# IceBoard-Rev2.net
KiCad netlist of a schematic drawn in EAGLE
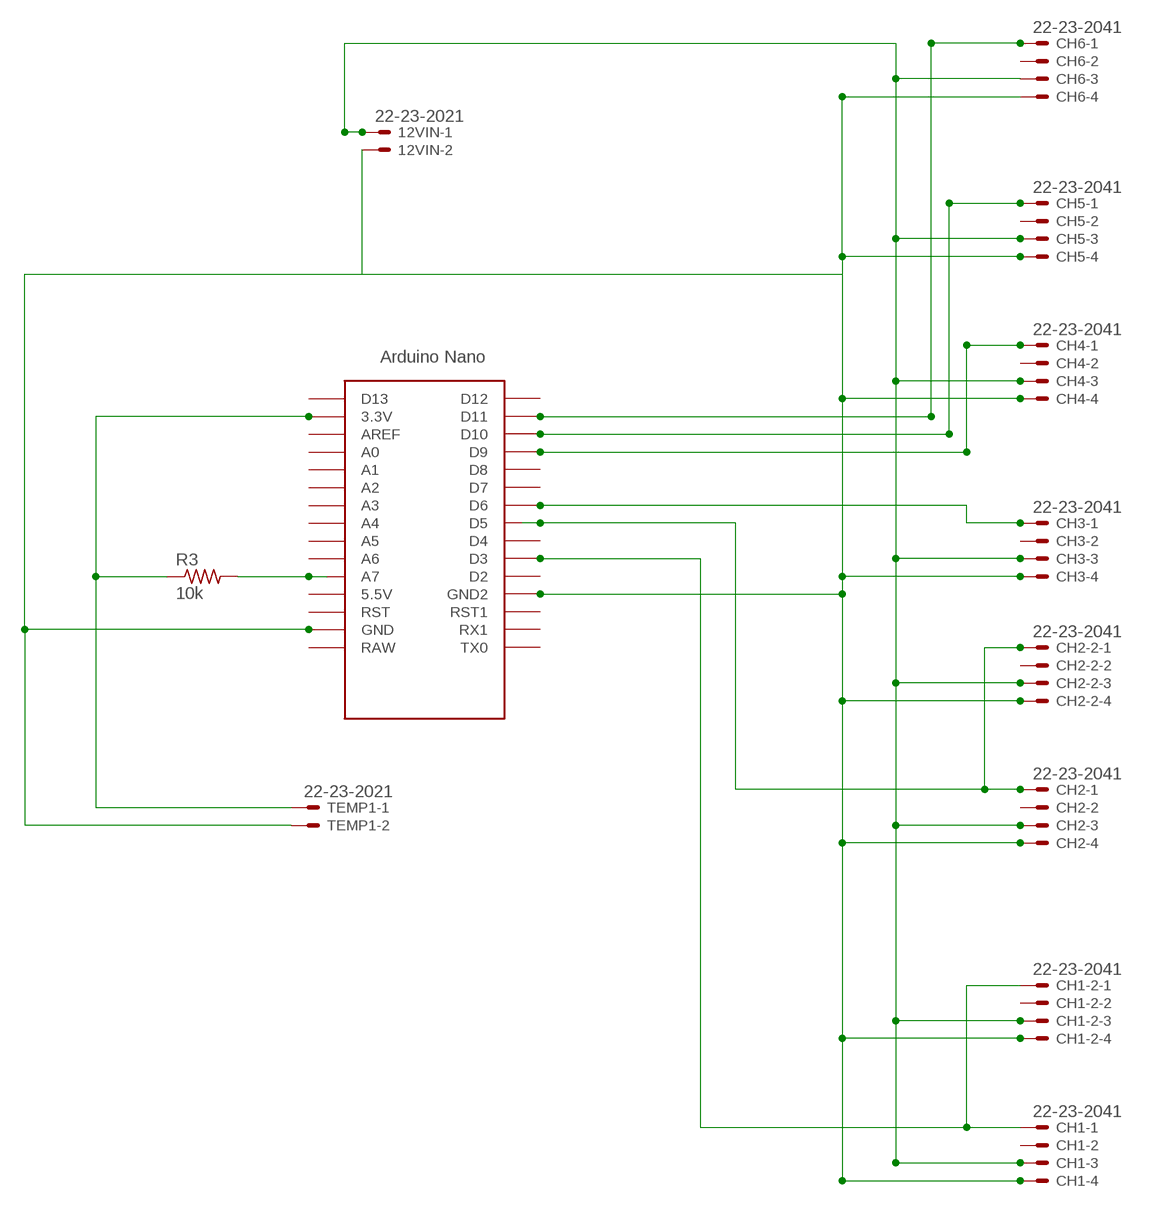
[diagram p0: schematic, sheet 1]

(export (version "E")
  (design (tool "Eeschema 10.0.6"))
  (components
    (comp (ref "12VIN")
      (value "22-23-2021")
      (footprint "eagle-import:22-23-2021")
      (fields (field (name "MF") "MOLEX"))
      (libsource (lib "eagle-import") (part "22-23-2021"))
    )
    (comp (ref "CH1")
      (value "22-23-2041")
      (footprint "eagle-import:22-23-2041")
      (fields (field (name "MF") "MOLEX"))
      (libsource (lib "eagle-import") (part "22-23-2041"))
    )
    (comp (ref "CH1-2")
      (value "22-23-2041")
      (footprint "eagle-import:22-23-2041")
      (fields (field (name "MF") "MOLEX"))
      (libsource (lib "eagle-import") (part "22-23-2041"))
    )
    (comp (ref "CH2")
      (value "22-23-2041")
      (footprint "eagle-import:22-23-2041")
      (fields (field (name "MF") "MOLEX"))
      (libsource (lib "eagle-import") (part "22-23-2041"))
    )
    (comp (ref "CH2-2")
      (value "22-23-2041")
      (footprint "eagle-import:22-23-2041")
      (fields (field (name "MF") "MOLEX"))
      (libsource (lib "eagle-import") (part "22-23-2041"))
    )
    (comp (ref "CH3")
      (value "22-23-2041")
      (footprint "eagle-import:22-23-2041")
      (fields (field (name "MF") "MOLEX"))
      (libsource (lib "eagle-import") (part "22-23-2041"))
    )
    (comp (ref "CH4")
      (value "22-23-2041")
      (footprint "eagle-import:22-23-2041")
      (fields (field (name "MF") "MOLEX"))
      (libsource (lib "eagle-import") (part "22-23-2041"))
    )
    (comp (ref "CH5")
      (value "22-23-2041")
      (footprint "eagle-import:22-23-2041")
      (fields (field (name "MF") "MOLEX"))
      (libsource (lib "eagle-import") (part "22-23-2041"))
    )
    (comp (ref "CH6")
      (value "22-23-2041")
      (footprint "eagle-import:22-23-2041")
      (fields (field (name "MF") "MOLEX"))
      (libsource (lib "eagle-import") (part "22-23-2041"))
    )
    (comp (ref "R3")
      (value "10k")
      (footprint "eagle-import:R0805")
      (libsource (lib "eagle-import") (part "R-US_R0805"))
    )
    (comp (ref "TEMP1")
      (value "22-23-2021")
      (footprint "eagle-import:22-23-2021")
      (fields (field (name "MF") "MOLEX"))
      (libsource (lib "eagle-import") (part "22-23-2021"))
    )
    (comp (ref "U$1")
      (value "NANO")
      (footprint "eagle-import:NANO")
      (libsource (lib "eagle-import") (part "NANO"))
    )
  )
  (nets
    (net (code "1") (name "Net-(12VINA-S)") (class "Default")
      (node (ref "12VIN") (pin "1") (pinfunction "S_1") (pintype "passive"))
      (node (ref "CH1") (pin "3") (pinfunction "S_3") (pintype "passive"))
      (node (ref "CH1-2") (pin "3") (pinfunction "S_3") (pintype "passive"))
      (node (ref "CH2") (pin "3") (pinfunction "S_3") (pintype "passive"))
      (node (ref "CH2-2") (pin "3") (pinfunction "S_3") (pintype "passive"))
      (node (ref "CH3") (pin "3") (pinfunction "S_3") (pintype "passive"))
      (node (ref "CH4") (pin "3") (pinfunction "S_3") (pintype "passive"))
      (node (ref "CH5") (pin "3") (pinfunction "S_3") (pintype "passive"))
      (node (ref "CH6") (pin "3") (pinfunction "S_3") (pintype "passive"))
    )
    (net (code "2") (name "Net-(12VINB-S)") (class "Default")
      (node (ref "12VIN") (pin "2") (pinfunction "S_2") (pintype "passive"))
      (node (ref "CH1") (pin "4") (pinfunction "S_4") (pintype "passive"))
      (node (ref "CH1-2") (pin "4") (pinfunction "S_4") (pintype "passive"))
      (node (ref "CH2") (pin "4") (pinfunction "S_4") (pintype "passive"))
      (node (ref "CH2-2") (pin "4") (pinfunction "S_4") (pintype "passive"))
      (node (ref "CH3") (pin "4") (pinfunction "S_4") (pintype "passive"))
      (node (ref "CH4") (pin "4") (pinfunction "S_4") (pintype "passive"))
      (node (ref "CH5") (pin "4") (pinfunction "S_4") (pintype "passive"))
      (node (ref "CH6") (pin "4") (pinfunction "S_4") (pintype "passive"))
      (node (ref "TEMP1") (pin "2") (pinfunction "S_2") (pintype "passive"))
      (node (ref "U$1") (pin "GND") (pinfunction "GND_GND") (pintype "bidirectional"))
      (node (ref "U$1") (pin "GND1") (pinfunction "GND2_GND1") (pintype "bidirectional"))
    )
    (net (code "3") (name "Net-(CH1-2A-S)") (class "Default")
      (node (ref "CH1") (pin "1") (pinfunction "S_1") (pintype "passive"))
      (node (ref "CH1-2") (pin "1") (pinfunction "S_1") (pintype "passive"))
      (node (ref "U$1") (pin "D3") (pinfunction "D3_D3") (pintype "bidirectional"))
    )
    (net (code "4") (name "Net-(CH2-2A-S)") (class "Default")
      (node (ref "CH2") (pin "1") (pinfunction "S_1") (pintype "passive"))
      (node (ref "CH2-2") (pin "1") (pinfunction "S_1") (pintype "passive"))
      (node (ref "U$1") (pin "D5") (pinfunction "D5_D5") (pintype "bidirectional"))
    )
    (net (code "5") (name "Net-(CH3A-S)") (class "Default")
      (node (ref "CH3") (pin "1") (pinfunction "S_1") (pintype "passive"))
      (node (ref "U$1") (pin "D6") (pinfunction "D6_D6") (pintype "bidirectional"))
    )
    (net (code "6") (name "Net-(CH4A-S)") (class "Default")
      (node (ref "CH4") (pin "1") (pinfunction "S_1") (pintype "passive"))
      (node (ref "U$1") (pin "D9") (pinfunction "D9_D9") (pintype "bidirectional"))
    )
    (net (code "7") (name "Net-(CH5A-S)") (class "Default")
      (node (ref "CH5") (pin "1") (pinfunction "S_1") (pintype "passive"))
      (node (ref "U$1") (pin "D10") (pinfunction "D10_D10") (pintype "bidirectional"))
    )
    (net (code "8") (name "Net-(CH6A-S)") (class "Default")
      (node (ref "CH6") (pin "1") (pinfunction "S_1") (pintype "passive"))
      (node (ref "U$1") (pin "D11") (pinfunction "D11_D11") (pintype "bidirectional"))
    )
    (net (code "9") (name "Net-(R3-Pad2)") (class "Default")
      (node (ref "R3") (pin "2") (pinfunction "2_2") (pintype "passive"))
      (node (ref "U$1") (pin "A7") (pinfunction "A7_A7") (pintype "bidirectional"))
    )
    (net (code "10") (name "Net-(TEMP1A-S)") (class "Default")
      (node (ref "R3") (pin "1") (pinfunction "1_1") (pintype "passive"))
      (node (ref "TEMP1") (pin "1") (pinfunction "S_1") (pintype "passive"))
      (node (ref "U$1") (pin "3.3V") (pinfunction "3.3V_3.3V") (pintype "bidirectional"))
    )
    (net (code "11") (name "unconnected-(CH1-2B-S-Pad2)") (class "Default")
      (node (ref "CH1-2") (pin "2") (pinfunction "S_2") (pintype "passive"))
    )
    (net (code "12") (name "unconnected-(CH1B-S-Pad2)") (class "Default")
      (node (ref "CH1") (pin "2") (pinfunction "S_2") (pintype "passive"))
    )
    (net (code "13") (name "unconnected-(CH2-2B-S-Pad2)") (class "Default")
      (node (ref "CH2-2") (pin "2") (pinfunction "S_2") (pintype "passive"))
    )
    (net (code "14") (name "unconnected-(CH2B-S-Pad2)") (class "Default")
      (node (ref "CH2") (pin "2") (pinfunction "S_2") (pintype "passive"))
    )
    (net (code "15") (name "unconnected-(CH3B-S-Pad2)") (class "Default")
      (node (ref "CH3") (pin "2") (pinfunction "S_2") (pintype "passive"))
    )
    (net (code "16") (name "unconnected-(CH4B-S-Pad2)") (class "Default")
      (node (ref "CH4") (pin "2") (pinfunction "S_2") (pintype "passive"))
    )
    (net (code "17") (name "unconnected-(CH5B-S-Pad2)") (class "Default")
      (node (ref "CH5") (pin "2") (pinfunction "S_2") (pintype "passive"))
    )
    (net (code "18") (name "unconnected-(CH6B-S-Pad2)") (class "Default")
      (node (ref "CH6") (pin "2") (pinfunction "S_2") (pintype "passive"))
    )
    (net (code "19") (name "unconnected-(U$1-5.5V-Pad5V)") (class "Default")
      (node (ref "U$1") (pin "5V") (pinfunction "5.5V_5V") (pintype "bidirectional"))
    )
    (net (code "20") (name "unconnected-(U$1-PadA0)") (class "Default")
      (node (ref "U$1") (pin "A0") (pinfunction "A0_A0") (pintype "bidirectional"))
    )
    (net (code "21") (name "unconnected-(U$1-PadA1)") (class "Default")
      (node (ref "U$1") (pin "A1") (pinfunction "A1_A1") (pintype "bidirectional"))
    )
    (net (code "22") (name "unconnected-(U$1-PadA2)") (class "Default")
      (node (ref "U$1") (pin "A2") (pinfunction "A2_A2") (pintype "bidirectional"))
    )
    (net (code "23") (name "unconnected-(U$1-PadA3)") (class "Default")
      (node (ref "U$1") (pin "A3") (pinfunction "A3_A3") (pintype "bidirectional"))
    )
    (net (code "24") (name "unconnected-(U$1-PadA4)") (class "Default")
      (node (ref "U$1") (pin "A4") (pinfunction "A4_A4") (pintype "bidirectional"))
    )
    (net (code "25") (name "unconnected-(U$1-PadA5)") (class "Default")
      (node (ref "U$1") (pin "A5") (pinfunction "A5_A5") (pintype "bidirectional"))
    )
    (net (code "26") (name "unconnected-(U$1-PadA6)") (class "Default")
      (node (ref "U$1") (pin "A6") (pinfunction "A6_A6") (pintype "bidirectional"))
    )
    (net (code "27") (name "unconnected-(U$1-PadAREF)") (class "Default")
      (node (ref "U$1") (pin "AREF") (pinfunction "AREF_AREF") (pintype "bidirectional"))
    )
    (net (code "28") (name "unconnected-(U$1-PadD2)") (class "Default")
      (node (ref "U$1") (pin "D2") (pinfunction "D2_D2") (pintype "bidirectional"))
    )
    (net (code "29") (name "unconnected-(U$1-PadD4)") (class "Default")
      (node (ref "U$1") (pin "D4") (pinfunction "D4_D4") (pintype "bidirectional"))
    )
    (net (code "30") (name "unconnected-(U$1-PadD7)") (class "Default")
      (node (ref "U$1") (pin "D7") (pinfunction "D7_D7") (pintype "bidirectional"))
    )
    (net (code "31") (name "unconnected-(U$1-PadD8)") (class "Default")
      (node (ref "U$1") (pin "D8") (pinfunction "D8_D8") (pintype "bidirectional"))
    )
    (net (code "32") (name "unconnected-(U$1-PadD12)") (class "Default")
      (node (ref "U$1") (pin "D12") (pinfunction "D12_D12") (pintype "bidirectional"))
    )
    (net (code "33") (name "unconnected-(U$1-PadD13)") (class "Default")
      (node (ref "U$1") (pin "D13") (pinfunction "D13_D13") (pintype "bidirectional"))
    )
    (net (code "34") (name "unconnected-(U$1-PadICSP1)") (class "Default")
      (node (ref "U$1") (pin "ICSP1") (pinfunction "ICSP1_ICSP1") (pintype "bidirectional"))
    )
    (net (code "35") (name "unconnected-(U$1-PadICSP2)") (class "Default")
      (node (ref "U$1") (pin "ICSP2") (pinfunction "ICSP2_ICSP2") (pintype "bidirectional"))
    )
    (net (code "36") (name "unconnected-(U$1-PadICSP3)") (class "Default")
      (node (ref "U$1") (pin "ICSP3") (pinfunction "ICSP3_ICSP3") (pintype "bidirectional"))
    )
    (net (code "37") (name "unconnected-(U$1-PadICSP4)") (class "Default")
      (node (ref "U$1") (pin "ICSP4") (pinfunction "ICSP4_ICSP4") (pintype "bidirectional"))
    )
    (net (code "38") (name "unconnected-(U$1-PadICSP5)") (class "Default")
      (node (ref "U$1") (pin "ICSP5") (pinfunction "ICSP5_ICSP5") (pintype "bidirectional"))
    )
    (net (code "39") (name "unconnected-(U$1-PadICSP6)") (class "Default")
      (node (ref "U$1") (pin "ICSP6") (pinfunction "ICSP6_ICSP6") (pintype "bidirectional"))
    )
    (net (code "40") (name "unconnected-(U$1-PadRAW)") (class "Default")
      (node (ref "U$1") (pin "RAW") (pinfunction "RAW_RAW") (pintype "bidirectional"))
    )
    (net (code "41") (name "unconnected-(U$1-PadRST)") (class "Default")
      (node (ref "U$1") (pin "RST") (pinfunction "RST_RST") (pintype "bidirectional"))
    )
    (net (code "42") (name "unconnected-(U$1-PadRST1)") (class "Default")
      (node (ref "U$1") (pin "RST1") (pinfunction "RST1_RST1") (pintype "bidirectional"))
    )
    (net (code "43") (name "unconnected-(U$1-PadRX1)") (class "Default")
      (node (ref "U$1") (pin "RX1") (pinfunction "RX1_RX1") (pintype "bidirectional"))
    )
    (net (code "44") (name "unconnected-(U$1-PadTX0)") (class "Default")
      (node (ref "U$1") (pin "TX0") (pinfunction "TX0_TX0") (pintype "bidirectional"))
    )
  )
)
